# SCH_acpi-pcb-design.net
KiCad netlist of a schematic drawn in EasyEDA
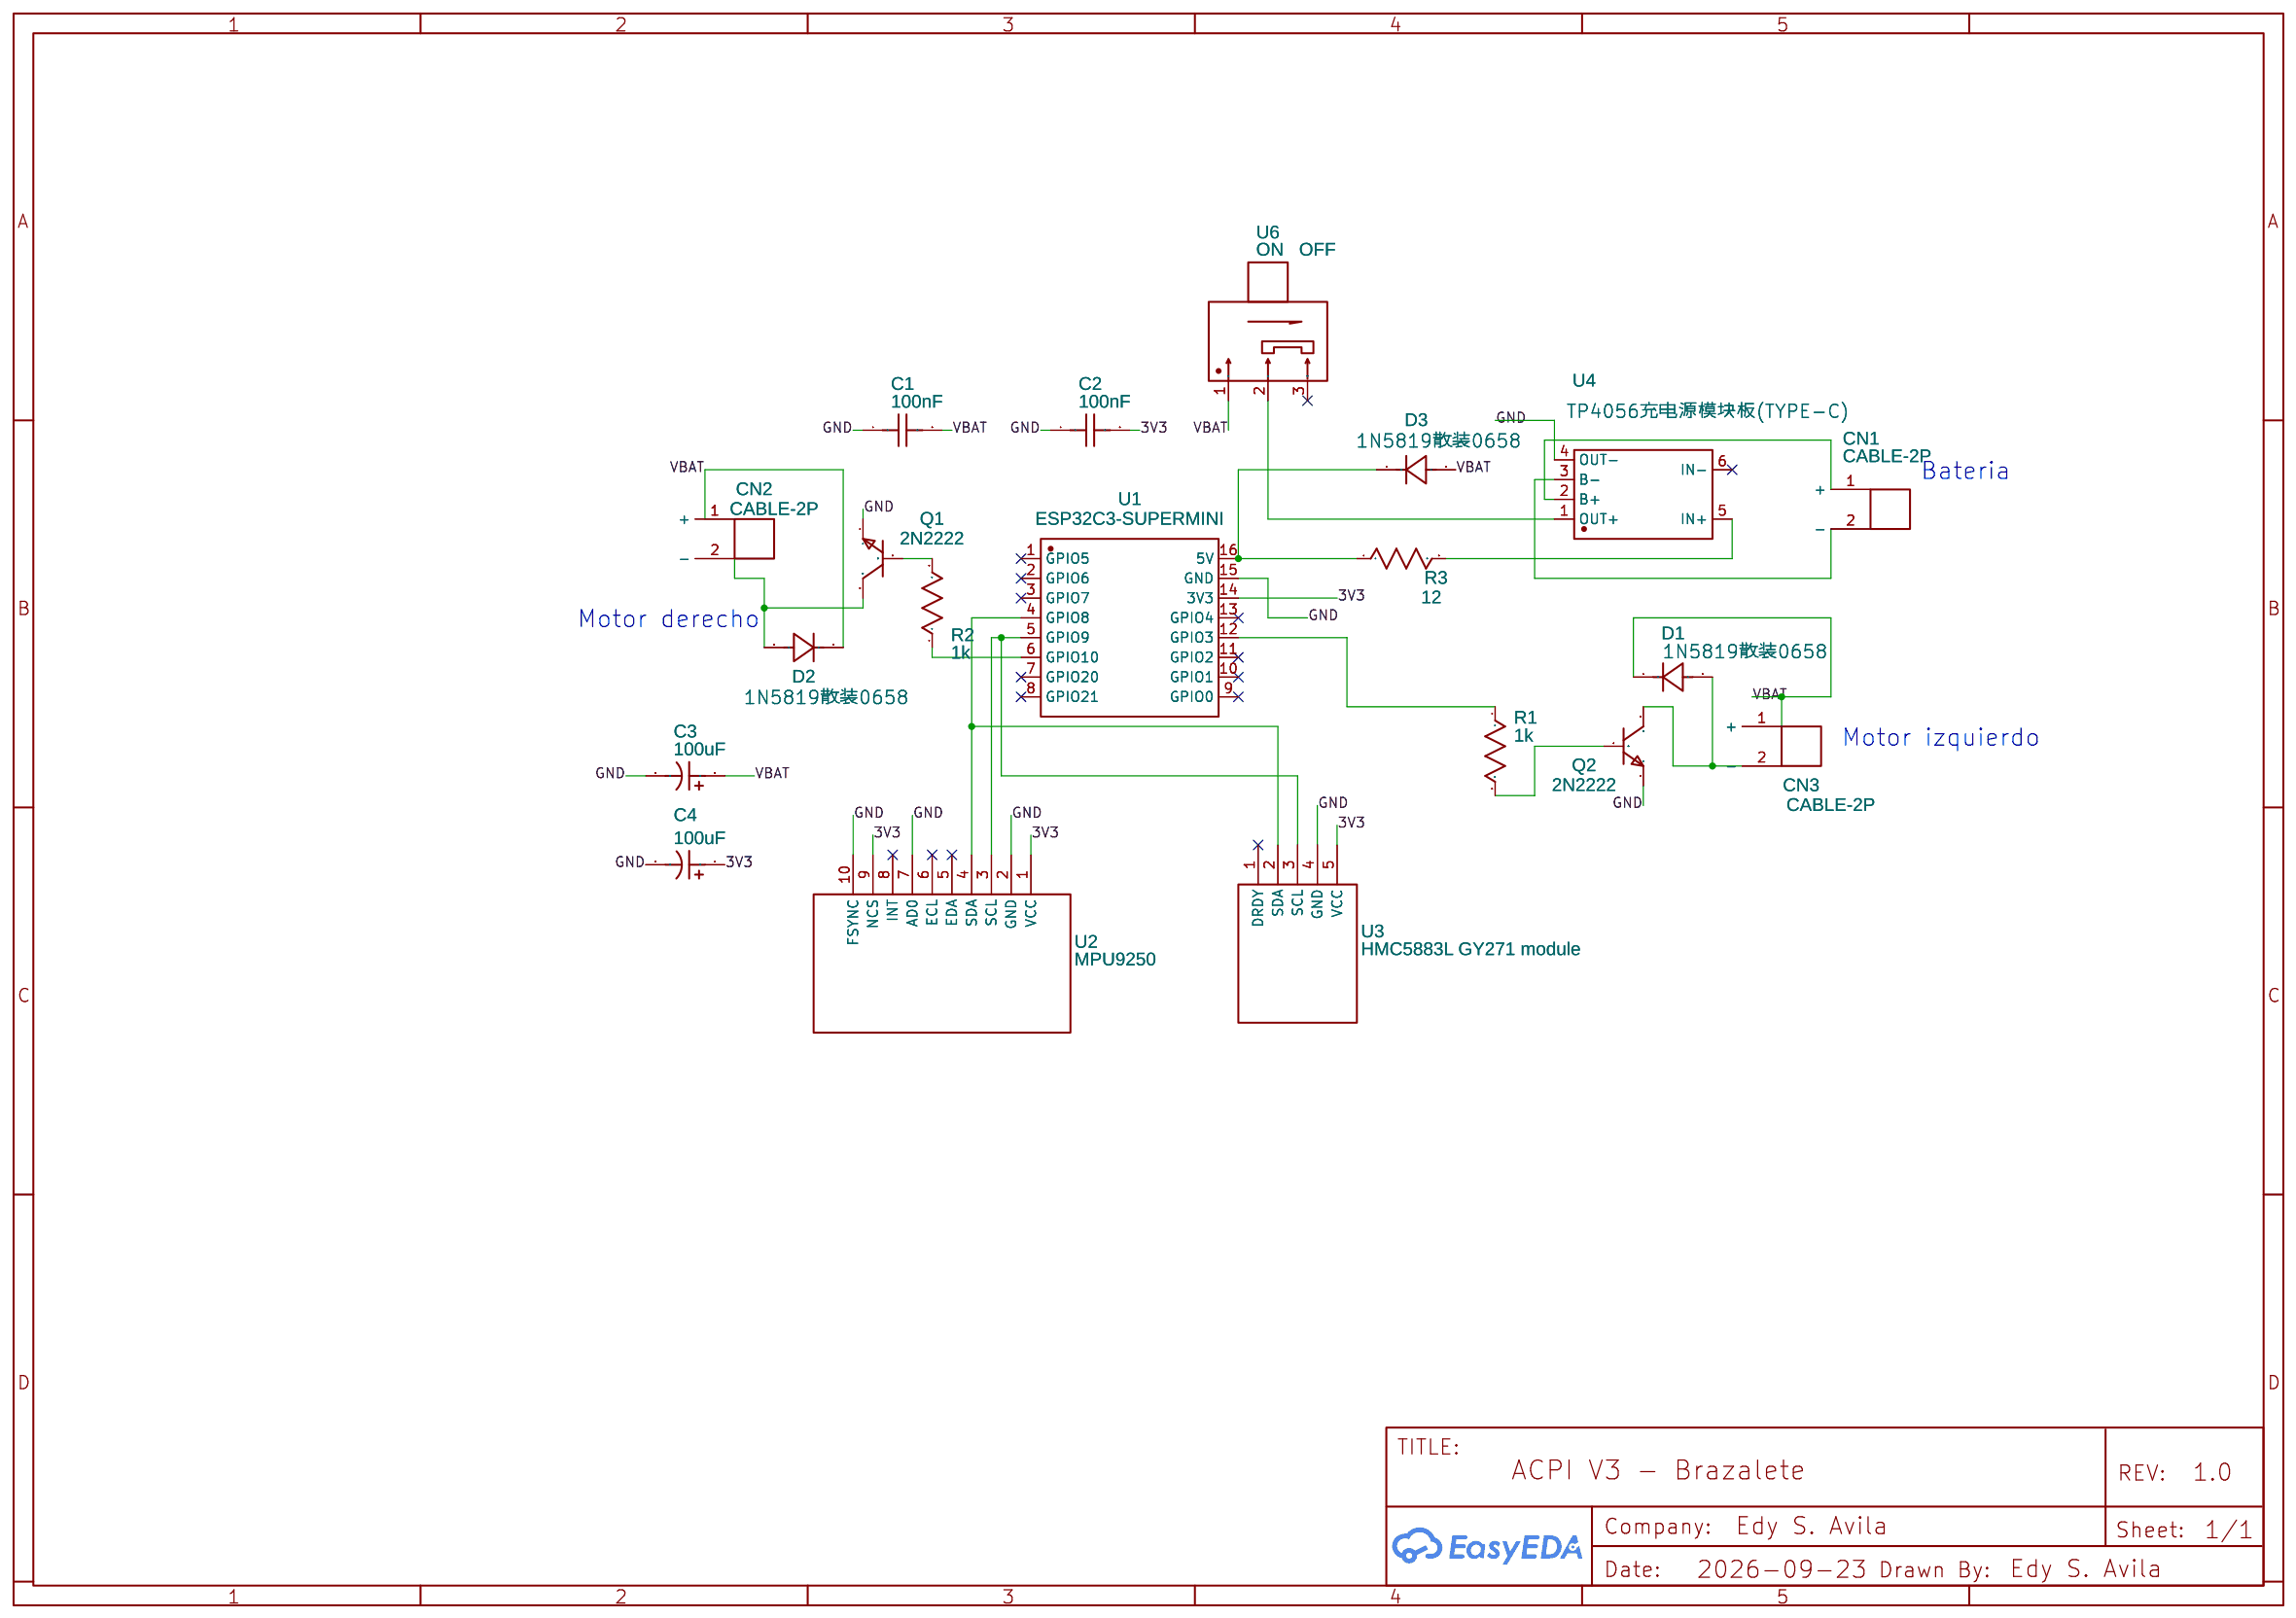
[diagram p0: schematic sheet]

(export (version "E")
  (design (tool "Eeschema 10.0.6"))
  (components
    (comp (ref "C1")
      (value "100nF")
      (fields
        (field (name "Manufacturer Part") "CC2A104ZC1ID3F7C30MF")
        (field (name "Manufacturer") "Dersonic(德尔创)")
      )
      (libsource (lib "") (part "CC2A104ZC1ID3F7C30MF"))
    )
    (comp (ref "C2")
      (value "100nF")
      (fields
        (field (name "Manufacturer Part") "CC2A104ZC1ID3F7C30MF")
        (field (name "Manufacturer") "Dersonic(德尔创)")
      )
      (libsource (lib "") (part "CC2A104ZC1ID3F7C30MF"))
    )
    (comp (ref "C3")
      (value "100uF")
      (fields (field (name "Manufacturer Part") "OLKC1102A220MF") (field (name "Manufacturer") "Ymin(永铭)"))
      (libsource (lib "") (part "OLKC1102A220MF"))
    )
    (comp (ref "C4")
      (value "100uF")
      (fields (field (name "Manufacturer Part") "OLKC1102A220MF") (field (name "Manufacturer") "Ymin(永铭)"))
      (libsource (lib "") (part "OLKC1102A220MF"))
    )
    (comp (ref "CN1") (value "CABLE-2P") (libsource (lib "") (part "CABLE-2P")))
    (comp (ref "CN2") (value "CABLE-2P") (libsource (lib "") (part "CABLE-2P")))
    (comp (ref "CN3") (value "CABLE-2P") (libsource (lib "") (part "CABLE-2P")))
    (comp (ref "D1")
      (value "1N5819散装0658")
      (fields (field (name "Manufacturer") "YFW(佑风微)"))
      (libsource (lib "") (part "1N5819散装0658_1"))
    )
    (comp (ref "D2")
      (value "1N5819散装0658")
      (fields (field (name "Manufacturer") "YFW(佑风微)"))
      (libsource (lib "") (part "1N5819散装0658"))
    )
    (comp (ref "D3")
      (value "1N5819散装0658")
      (fields (field (name "Manufacturer") "YFW(佑风微)"))
      (libsource (lib "") (part "1N5819散装0658_1"))
    )
    (comp (ref "Q1")
      (value "2N2222")
      (fields (field (name "Manufacturer Part") "2N2222A") (field (name "Manufacturer") "ST(先科)"))
      (libsource (lib "") (part "2N2222_1"))
    )
    (comp (ref "Q2")
      (value "2N2222")
      (fields (field (name "Manufacturer Part") "2N2222A") (field (name "Manufacturer") "ST(先科)"))
      (libsource (lib "") (part "2N2222"))
    )
    (comp (ref "R1") (value "1k") (libsource (lib "") (part "resistence_2")))
    (comp (ref "R2") (value "1k") (libsource (lib "") (part "resistence")))
    (comp (ref "R3") (value "12") (libsource (lib "") (part "resistence_1")))
    (comp (ref "U1")
      (value "ESP32C3-SUPERMINI")
      (fields (field (name "Manufacturer Part") "ESP32C3-SuperMini"))
      (libsource (lib "") (part "ESP32C3-SUPERMINI"))
    )
    (comp (ref "U2") (value "MPU9250") (libsource (lib "") (part "MPU9250")))
    (comp (ref "U3") (value "HMC5883L GY271 module") (libsource (lib "") (part "HMC5883L GY271 module")))
    (comp (ref "U4")
      (value "TP4056充电源模块板(TYPE-C)")
      (fields (field (name "Manufacturer Part") "TP4056充电源模块板(Type-C)"))
      (libsource (lib "") (part "TP4056充电源模块板(TYPE-C)"))
    )
    (comp (ref "U6")
      (value "ON   OFF")
      (fields (field (name "Manufacturer Part") "SS12D00G4") (field (name "Manufacturer") "YIZHI(逸致)"))
      (libsource (lib "") (part "SS12D00G4"))
    )
  )
  (nets
    (net (code "1") (name "/3V3") (class "Default")
      (node (ref "C2") (pin "2") (pinfunction "2_2") (pintype "unspecified"))
      (node (ref "C4") (pin "1") (pinfunction "1_1") (pintype "input"))
      (node (ref "U1") (pin "14") (pinfunction "3V3_14") (pintype "unspecified"))
      (node (ref "U2") (pin "1") (pinfunction "VCC_1") (pintype "unspecified"))
      (node (ref "U2") (pin "9") (pinfunction "NCS_9") (pintype "unspecified"))
      (node (ref "U3") (pin "5") (pinfunction "VCC_5") (pintype "unspecified"))
    )
    (net (code "2") (name "/GND") (class "Default")
      (node (ref "C1") (pin "1") (pinfunction "1_1") (pintype "unspecified"))
      (node (ref "C2") (pin "1") (pinfunction "1_1") (pintype "unspecified"))
      (node (ref "C3") (pin "2") (pinfunction "2_2") (pintype "input"))
      (node (ref "C4") (pin "2") (pinfunction "2_2") (pintype "input"))
      (node (ref "Q1") (pin "1") (pinfunction "E_1") (pintype "unspecified"))
      (node (ref "Q2") (pin "1") (pinfunction "E_1") (pintype "unspecified"))
      (node (ref "U1") (pin "15") (pinfunction "GND_15") (pintype "unspecified"))
      (node (ref "U2") (pin "10") (pinfunction "FSYNC_10") (pintype "unspecified"))
      (node (ref "U2") (pin "2") (pinfunction "GND_2") (pintype "unspecified"))
      (node (ref "U2") (pin "7") (pinfunction "AD0_7") (pintype "unspecified"))
      (node (ref "U3") (pin "4") (pinfunction "GND_4") (pintype "unspecified"))
      (node (ref "U4") (pin "4") (pinfunction "OUT-_4") (pintype "unspecified"))
    )
    (net (code "3") (name "/VBAT") (class "Default")
      (node (ref "C1") (pin "2") (pinfunction "2_2") (pintype "unspecified"))
      (node (ref "C3") (pin "1") (pinfunction "1_1") (pintype "input"))
      (node (ref "CN2") (pin "1") (pinfunction "+_1") (pintype "unspecified"))
      (node (ref "CN3") (pin "1") (pinfunction "+_1") (pintype "unspecified"))
      (node (ref "D1") (pin "1") (pinfunction "K_1") (pintype "unspecified"))
      (node (ref "D2") (pin "1") (pinfunction "K_1") (pintype "unspecified"))
      (node (ref "D3") (pin "2") (pinfunction "A_2") (pintype "unspecified"))
      (node (ref "U6") (pin "1") (pinfunction "1_1") (pintype "unspecified"))
    )
    (net (code "4") (name "Net-(CN1-+)") (class "Default")
      (node (ref "CN1") (pin "1") (pinfunction "+_1") (pintype "unspecified"))
      (node (ref "U4") (pin "2") (pinfunction "B+_2") (pintype "unspecified"))
    )
    (net (code "5") (name "Net-(CN1--)") (class "Default")
      (node (ref "CN1") (pin "2") (pinfunction "-_2") (pintype "unspecified"))
      (node (ref "U4") (pin "3") (pinfunction "B-_3") (pintype "unspecified"))
    )
    (net (code "6") (name "Net-(CN2--)") (class "Default")
      (node (ref "CN2") (pin "2") (pinfunction "-_2") (pintype "unspecified"))
      (node (ref "D2") (pin "2") (pinfunction "A_2") (pintype "unspecified"))
      (node (ref "Q1") (pin "3") (pinfunction "C_3") (pintype "unspecified"))
    )
    (net (code "7") (name "Net-(CN3--)") (class "Default")
      (node (ref "CN3") (pin "2") (pinfunction "-_2") (pintype "unspecified"))
      (node (ref "D1") (pin "2") (pinfunction "A_2") (pintype "unspecified"))
      (node (ref "Q2") (pin "3") (pinfunction "C_3") (pintype "unspecified"))
    )
    (net (code "8") (name "Net-(D3-K)") (class "Default")
      (node (ref "D3") (pin "1") (pinfunction "K_1") (pintype "unspecified"))
      (node (ref "R3") (pin "1") (pinfunction "1_1") (pintype "unspecified"))
      (node (ref "U1") (pin "16") (pinfunction "5V_16") (pintype "unspecified"))
    )
    (net (code "9") (name "Net-(Q1-B)") (class "Default")
      (node (ref "Q1") (pin "2") (pinfunction "B_2") (pintype "unspecified"))
      (node (ref "R2") (pin "2") (pinfunction "2_2") (pintype "unspecified"))
    )
    (net (code "10") (name "Net-(Q2-B)") (class "Default")
      (node (ref "Q2") (pin "2") (pinfunction "B_2") (pintype "unspecified"))
      (node (ref "R1") (pin "2") (pinfunction "2_2") (pintype "unspecified"))
    )
    (net (code "11") (name "Net-(U1-GPIO3)") (class "Default")
      (node (ref "R1") (pin "1") (pinfunction "1_1") (pintype "unspecified"))
      (node (ref "U1") (pin "12") (pinfunction "GPIO3_12") (pintype "unspecified"))
    )
    (net (code "12") (name "Net-(U1-GPIO8)") (class "Default")
      (node (ref "U1") (pin "4") (pinfunction "GPIO8_4") (pintype "unspecified"))
      (node (ref "U2") (pin "4") (pinfunction "SDA_4") (pintype "unspecified"))
      (node (ref "U3") (pin "2") (pinfunction "SDA_2") (pintype "unspecified"))
    )
    (net (code "13") (name "Net-(U1-GPIO9)") (class "Default")
      (node (ref "U1") (pin "5") (pinfunction "GPIO9_5") (pintype "unspecified"))
      (node (ref "U2") (pin "3") (pinfunction "SCL_3") (pintype "unspecified"))
      (node (ref "U3") (pin "3") (pinfunction "SCL_3") (pintype "unspecified"))
    )
    (net (code "14") (name "Net-(U1-GPIO10)") (class "Default")
      (node (ref "R2") (pin "1") (pinfunction "1_1") (pintype "unspecified"))
      (node (ref "U1") (pin "6") (pinfunction "GPIO10_6") (pintype "unspecified"))
    )
    (net (code "15") (name "Net-(U4-IN+)") (class "Default")
      (node (ref "R3") (pin "2") (pinfunction "2_2") (pintype "unspecified"))
      (node (ref "U4") (pin "5") (pinfunction "IN+_5") (pintype "unspecified"))
    )
    (net (code "16") (name "Net-(U4-OUT+)") (class "Default")
      (node (ref "U4") (pin "1") (pinfunction "OUT+_1") (pintype "unspecified"))
      (node (ref "U6") (pin "2") (pinfunction "2_2") (pintype "unspecified"))
    )
    (net (code "17") (name "unconnected-(U1-GPIO0-Pad9)") (class "Default")
      (node (ref "U1") (pin "9") (pinfunction "GPIO0_9") (pintype "unspecified+no_connect"))
    )
    (net (code "18") (name "unconnected-(U1-GPIO1-Pad10)") (class "Default")
      (node (ref "U1") (pin "10") (pinfunction "GPIO1_10") (pintype "unspecified+no_connect"))
    )
    (net (code "19") (name "unconnected-(U1-GPIO2-Pad11)") (class "Default")
      (node (ref "U1") (pin "11") (pinfunction "GPIO2_11") (pintype "unspecified+no_connect"))
    )
    (net (code "20") (name "unconnected-(U1-GPIO4-Pad13)") (class "Default")
      (node (ref "U1") (pin "13") (pinfunction "GPIO4_13") (pintype "unspecified+no_connect"))
    )
    (net (code "21") (name "unconnected-(U1-GPIO5-Pad1)") (class "Default")
      (node (ref "U1") (pin "1") (pinfunction "GPIO5_1") (pintype "unspecified+no_connect"))
    )
    (net (code "22") (name "unconnected-(U1-GPIO6-Pad2)") (class "Default")
      (node (ref "U1") (pin "2") (pinfunction "GPIO6_2") (pintype "unspecified+no_connect"))
    )
    (net (code "23") (name "unconnected-(U1-GPIO7-Pad3)") (class "Default")
      (node (ref "U1") (pin "3") (pinfunction "GPIO7_3") (pintype "unspecified+no_connect"))
    )
    (net (code "24") (name "unconnected-(U1-GPIO20-Pad7)") (class "Default")
      (node (ref "U1") (pin "7") (pinfunction "GPIO20_7") (pintype "unspecified+no_connect"))
    )
    (net (code "25") (name "unconnected-(U1-GPIO21-Pad8)") (class "Default")
      (node (ref "U1") (pin "8") (pinfunction "GPIO21_8") (pintype "unspecified+no_connect"))
    )
    (net (code "26") (name "unconnected-(U2-ECL-Pad6)") (class "Default")
      (node (ref "U2") (pin "6") (pinfunction "ECL_6") (pintype "unspecified+no_connect"))
    )
    (net (code "27") (name "unconnected-(U2-EDA-Pad5)") (class "Default")
      (node (ref "U2") (pin "5") (pinfunction "EDA_5") (pintype "unspecified+no_connect"))
    )
    (net (code "28") (name "unconnected-(U2-INT-Pad8)") (class "Default")
      (node (ref "U2") (pin "8") (pinfunction "INT_8") (pintype "unspecified+no_connect"))
    )
    (net (code "29") (name "unconnected-(U3-DRDY-Pad1)") (class "Default")
      (node (ref "U3") (pin "1") (pinfunction "DRDY_1") (pintype "unspecified+no_connect"))
    )
    (net (code "30") (name "unconnected-(U4-IN--Pad6)") (class "Default")
      (node (ref "U4") (pin "6") (pinfunction "IN-_6") (pintype "unspecified+no_connect"))
    )
    (net (code "31") (name "unconnected-(U6-Pad3)") (class "Default")
      (node (ref "U6") (pin "3") (pinfunction "3_3") (pintype "unspecified+no_connect"))
    )
  )
)
